# Sheet6.net
KiCad netlist of a schematic drawn in Altium Designer
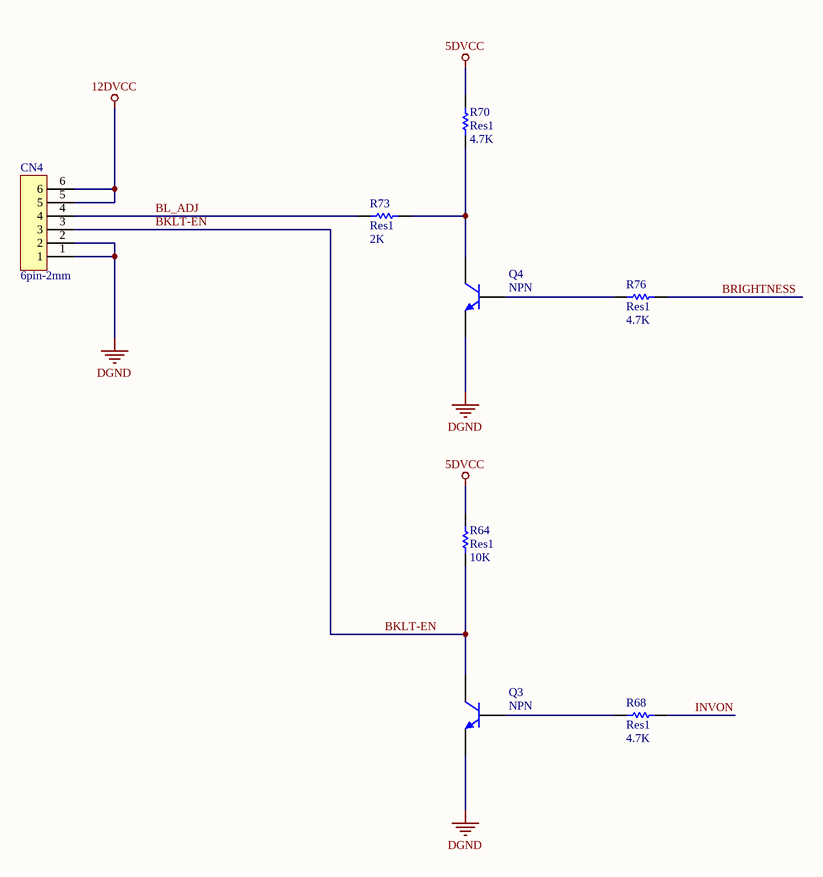
[diagram p0: Sheet6.SchDoc]

(export (version "E")
  (design (tool "Eeschema 10.0.6"))
  (components
    (comp (ref "CN4") (value "6pin-2mm") (footprint "JP-6") (libsource (lib "SCHLIB") (part "6pin-2mm")))
    (comp (ref "Q3")
      (value "NPN")
      (footprint "Q-SOT23")
      (description "NPN Bipolar Transistor")
      (fields (field (name "PUBLISHER") "Altium Limited"))
      (libsource (lib "Miscellaneous Devices") (part "NPN"))
    )
    (comp (ref "Q4")
      (value "NPN")
      (footprint "Q-SOT23")
      (description "NPN Bipolar Transistor")
      (fields (field (name "PUBLISHER") "Altium Limited"))
      (libsource (lib "Miscellaneous Devices") (part "NPN"))
    )
    (comp (ref "R64")
      (value "Res1")
      (footprint "R-0603")
      (description "Resistor")
      (fields (field (name "ALTIUM_VALUE") "10K") (field (name "PUBLISHER") "Altium Limited"))
      (libsource (lib "Miscellaneous Devices") (part "Res1"))
    )
    (comp (ref "R68")
      (value "Res1")
      (footprint "R-0603")
      (description "Resistor")
      (fields (field (name "ALTIUM_VALUE") "4.7K") (field (name "PUBLISHER") "Altium Limited"))
      (libsource (lib "Miscellaneous Devices") (part "Res1"))
    )
    (comp (ref "R70")
      (value "Res1")
      (footprint "R-0603")
      (description "Resistor")
      (fields (field (name "ALTIUM_VALUE") "4.7K") (field (name "PUBLISHER") "Altium Limited"))
      (libsource (lib "Miscellaneous Devices") (part "Res1"))
    )
    (comp (ref "R73")
      (value "Res1")
      (footprint "R-0603")
      (description "Resistor")
      (fields (field (name "ALTIUM_VALUE") "2K") (field (name "PUBLISHER") "Altium Limited"))
      (libsource (lib "Miscellaneous Devices") (part "Res1"))
    )
    (comp (ref "R76")
      (value "Res1")
      (footprint "R-0603")
      (description "Resistor")
      (fields (field (name "ALTIUM_VALUE") "4.7K") (field (name "PUBLISHER") "Altium Limited"))
      (libsource (lib "Miscellaneous Devices") (part "Res1"))
    )
  )
  (nets
    (net (code "1") (name "/BKLT-EN") (class "Default")
      (node (ref "CN4") (pin "3") (pinfunction "3_3") (pintype "passive"))
      (node (ref "Q3") (pin "1") (pinfunction "C_1") (pintype "passive"))
      (node (ref "R64") (pin "1") (pinfunction "1_1") (pintype "passive"))
    )
    (net (code "2") (name "/BL_ADJ") (class "Default")
      (node (ref "CN4") (pin "4") (pinfunction "4_4") (pintype "passive"))
      (node (ref "R73") (pin "1") (pinfunction "1_1") (pintype "passive"))
    )
    (net (code "3") (name "/BRIGHTNESS") (class "Default")
      (node (ref "R76") (pin "2") (pinfunction "2_2") (pintype "passive"))
    )
    (net (code "4") (name "/INVON") (class "Default")
      (node (ref "R68") (pin "2") (pinfunction "2_2") (pintype "passive"))
    )
    (net (code "5") (name "5DVCC") (class "Default")
      (node (ref "R64") (pin "2") (pinfunction "2_2") (pintype "passive"))
      (node (ref "R70") (pin "2") (pinfunction "2_2") (pintype "passive"))
    )
    (net (code "6") (name "12DVCC") (class "Default")
      (node (ref "CN4") (pin "5") (pinfunction "5_5") (pintype "passive"))
      (node (ref "CN4") (pin "6") (pinfunction "6_6") (pintype "passive"))
    )
    (net (code "7") (name "DGND") (class "Default")
      (node (ref "CN4") (pin "1") (pinfunction "1_1") (pintype "passive"))
      (node (ref "CN4") (pin "2") (pinfunction "2_2") (pintype "passive"))
      (node (ref "Q3") (pin "3") (pinfunction "E_3") (pintype "passive"))
      (node (ref "Q4") (pin "3") (pinfunction "E_3") (pintype "passive"))
    )
    (net (code "8") (name "Net-(Q3-B)") (class "Default")
      (node (ref "Q3") (pin "2") (pinfunction "B_2") (pintype "passive"))
      (node (ref "R68") (pin "1") (pinfunction "1_1") (pintype "passive"))
    )
    (net (code "9") (name "Net-(Q4-B)") (class "Default")
      (node (ref "Q4") (pin "2") (pinfunction "B_2") (pintype "passive"))
      (node (ref "R76") (pin "1") (pinfunction "1_1") (pintype "passive"))
    )
    (net (code "10") (name "Net-(Q4-C)") (class "Default")
      (node (ref "Q4") (pin "1") (pinfunction "C_1") (pintype "passive"))
      (node (ref "R70") (pin "1") (pinfunction "1_1") (pintype "passive"))
      (node (ref "R73") (pin "2") (pinfunction "2_2") (pintype "passive"))
    )
  )
)
